# PSU_-_BUCK_LDO_CHARGER.net
KiCad netlist of a schematic drawn in Altium Designer
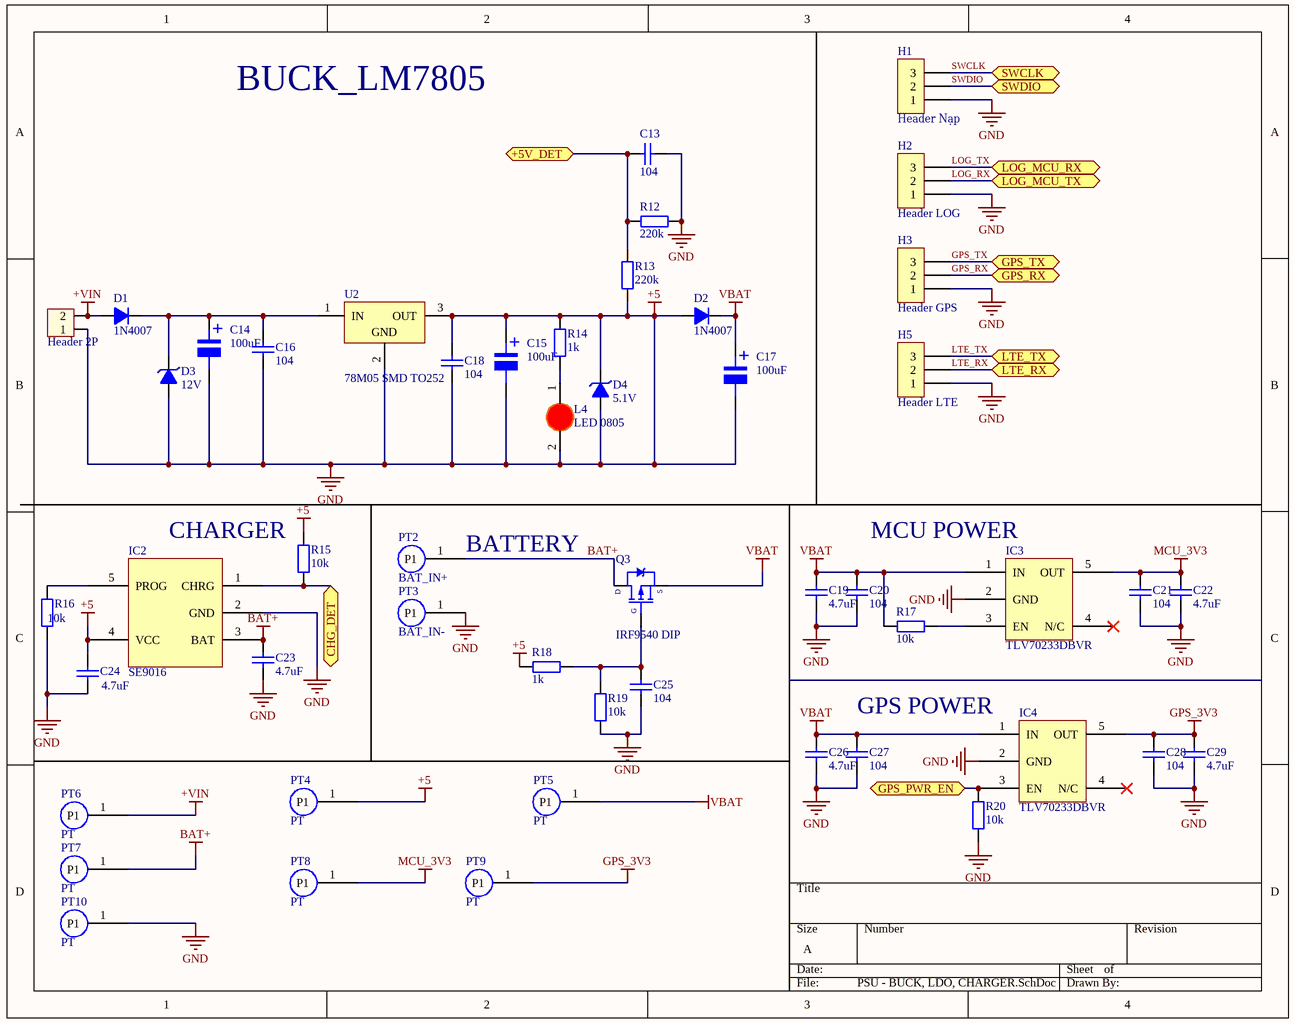
[diagram p0: PSU - BUCK, LDO, CHARGER.SchDoc]

(export (version "E")
  (design (tool "Eeschema 10.0.6"))
  (components
    (comp (ref "C13")
      (value "104")
      (footprint "tu 0805")
      (description "Dán")
      (libsource (lib "Altium_Lib_by_KhueNguyenCreator") (part "Tu 0805 104 50V 10%"))
    )
    (comp (ref "C14")
      (value "100uF")
      (footprint "tu nhom 6.3 (d)")
      (description "Dán")
      (libsource (lib "Altium_Lib_by_KhueNguyenCreator") (part "Tu Nhom 100uF 25V"))
    )
    (comp (ref "C15")
      (value "100uF")
      (footprint "tu nhom 6.3 (d)")
      (description "Dán")
      (libsource (lib "Altium_Lib_by_KhueNguyenCreator") (part "Tu Nhom 100uF 25V"))
    )
    (comp (ref "C16")
      (value "104")
      (footprint "tu 0805")
      (description "Dán")
      (libsource (lib "Altium_Lib_by_KhueNguyenCreator") (part "Tu 0805 104 50V 10%"))
    )
    (comp (ref "C17")
      (value "100uF")
      (footprint "tu nhom 6.3 (d)")
      (description "Dán")
      (libsource (lib "Altium_Lib_by_KhueNguyenCreator") (part "Tu Nhom 100uF 25V"))
    )
    (comp (ref "C18")
      (value "104")
      (footprint "tu 0805")
      (description "Dán")
      (libsource (lib "Altium_Lib_by_KhueNguyenCreator") (part "Tu 0805 104 50V 10%"))
    )
    (comp (ref "C19")
      (value "4.7uF")
      (footprint "tu 0805")
      (description "Dán")
      (libsource (lib "Altium_Lib_by_KhueNguyenCreator") (part "Tu 0805 475 25V 20%"))
    )
    (comp (ref "C20")
      (value "104")
      (footprint "tu 0805")
      (description "Dán")
      (libsource (lib "Altium_Lib_by_KhueNguyenCreator") (part "Tu 0805 104 50V 10%"))
    )
    (comp (ref "C21")
      (value "104")
      (footprint "tu 0805")
      (description "Dán")
      (libsource (lib "Altium_Lib_by_KhueNguyenCreator") (part "Tu 0805 104 50V 10%"))
    )
    (comp (ref "C22")
      (value "4.7uF")
      (footprint "tu 0805")
      (description "Dán")
      (libsource (lib "Altium_Lib_by_KhueNguyenCreator") (part "Tu 0805 475 25V 20%"))
    )
    (comp (ref "C23")
      (value "4.7uF")
      (footprint "tu 0805")
      (description "Dán")
      (libsource (lib "Altium_Lib_by_KhueNguyenCreator") (part "Tu 0805 475 25V 20%"))
    )
    (comp (ref "C24")
      (value "4.7uF")
      (footprint "tu 0805")
      (description "Dán")
      (libsource (lib "Altium_Lib_by_KhueNguyenCreator") (part "Tu 0805 475 25V 20%"))
    )
    (comp (ref "C25")
      (value "104")
      (footprint "tu 0805")
      (description "Dán")
      (libsource (lib "Altium_Lib_by_KhueNguyenCreator") (part "Tu 0805 104 50V 10%"))
    )
    (comp (ref "C26")
      (value "4.7uF")
      (footprint "tu 0805")
      (description "Dán")
      (libsource (lib "Altium_Lib_by_KhueNguyenCreator") (part "Tu 0805 475 25V 20%"))
    )
    (comp (ref "C27")
      (value "104")
      (footprint "tu 0805")
      (description "Dán")
      (libsource (lib "Altium_Lib_by_KhueNguyenCreator") (part "Tu 0805 104 50V 10%"))
    )
    (comp (ref "C28")
      (value "104")
      (footprint "tu 0805")
      (description "Dán")
      (libsource (lib "Altium_Lib_by_KhueNguyenCreator") (part "Tu 0805 104 50V 10%"))
    )
    (comp (ref "C29")
      (value "4.7uF")
      (footprint "tu 0805")
      (description "Dán")
      (libsource (lib "Altium_Lib_by_KhueNguyenCreator") (part "Tu 0805 475 25V 20%"))
    )
    (comp (ref "D1")
      (value "1N4007")
      (footprint "SODFL504X243-2N")
      (description "Cắm")
      (libsource (lib "Altium_Lib_by_KhueNguyenCreator") (part "Diode 1N4007"))
    )
    (comp (ref "D2")
      (value "1N4007")
      (footprint "SODFL504X243-2N")
      (description "Cắm")
      (libsource (lib "Altium_Lib_by_KhueNguyenCreator") (part "Diode 1N4007"))
    )
    (comp (ref "D3")
      (value "12V")
      (footprint "DIODE ZENNER SMD SOD80")
      (description "Dán")
      (libsource (lib "Altium_Lib_by_KhueNguyenCreator") (part "Diode Zener 12V"))
    )
    (comp (ref "D4")
      (value "5.1V")
      (footprint "DIODE ZENNER SMD SOD80")
      (description "Dán")
      (libsource (lib "Altium_Lib_by_KhueNguyenCreator") (part "Diode Zener 5.1V"))
    )
    (comp (ref "H1")
      (value "Header Nạp")
      (footprint "XH2.54M-3")
      (description "Cắm")
      (libsource (lib "Altium_Lib_by_KhueNguyenCreator") (part "Header 3P 2.54 Duc Thang"))
    )
    (comp (ref "H2")
      (value "Header LOG")
      (footprint "XH2.54M-3")
      (description "Cắm")
      (libsource (lib "Altium_Lib_by_KhueNguyenCreator") (part "Header 3P 2.54 Duc Thang"))
    )
    (comp (ref "H3")
      (value "Header GPS")
      (footprint "XH2.54M-3")
      (description "Cắm")
      (libsource (lib "Altium_Lib_by_KhueNguyenCreator") (part "Header 3P 2.54 Duc Thang"))
    )
    (comp (ref "H4")
      (value "Header 2P")
      (footprint "VH3.96M-2")
      (description "Cắm")
      (libsource (lib "Altium_Lib_by_KhueNguyenCreator") (part "Header 2P VH3.96 Duc Thang"))
    )
    (comp (ref "H5")
      (value "Header LTE")
      (footprint "XH2.54M-3")
      (description "Cắm")
      (libsource (lib "Altium_Lib_by_KhueNguyenCreator") (part "Header 3P 2.54 Duc Thang"))
    )
    (comp (ref "IC2")
      (value "SE9016")
      (footprint "SOT95P280X110-5N")
      (libsource (lib "Schlib2") (part "SE9016"))
    )
    (comp (ref "IC3")
      (value "TLV70233DBVR")
      (footprint "SOT95P280X145-5N")
      (libsource (lib "Schlib1") (part "TLV70233DBVR"))
    )
    (comp (ref "IC4")
      (value "TLV70233DBVR")
      (footprint "SOT95P280X145-5N")
      (libsource (lib "Schlib1") (part "TLV70233DBVR"))
    )
    (comp (ref "L4")
      (value "LED 0805")
      (footprint "LED-0805-Red")
      (description "Dán")
      (libsource (lib "Altium_Lib_by_KhueNguyenCreator") (part "LED 0805 Do"))
    )
    (comp (ref "PT2")
      (value "BAT_IN+")
      (footprint "Test pont")
      (libsource (lib "Test pont") (part "test pont"))
    )
    (comp (ref "PT3")
      (value "BAT_IN-")
      (footprint "Test pont")
      (libsource (lib "Test pont") (part "test pont"))
    )
    (comp (ref "PT4") (value "PT") (footprint "Test pont") (libsource (lib "Test pont") (part "test pont")))
    (comp (ref "PT5") (value "PT") (footprint "Test pont") (libsource (lib "Test pont") (part "test pont")))
    (comp (ref "PT6") (value "PT") (footprint "Test pont") (libsource (lib "Test pont") (part "test pont")))
    (comp (ref "PT7") (value "PT") (footprint "Test pont") (libsource (lib "Test pont") (part "test pont")))
    (comp (ref "PT8") (value "PT") (footprint "Test pont") (libsource (lib "Test pont") (part "test pont")))
    (comp (ref "PT9") (value "PT") (footprint "Test pont") (libsource (lib "Test pont") (part "test pont")))
    (comp (ref "PT10") (value "PT") (footprint "Test pont") (libsource (lib "Test pont") (part "test pont")))
    (comp (ref "Q3")
      (value "IRF9540 DIP")
      (footprint "DPAK254P1511X469-3N")
      (description "P-Channel Power MOSFET")
      (fields (field (name "PUBLISHER") "Altium Limited"))
      (libsource (lib "Altium_Lib_by_KhueNguyenCreator") (part "IRF9540 DIP"))
    )
    (comp (ref "R12")
      (value "220k")
      (footprint "tro smd 0805")
      (description "Dán")
      (libsource (lib "Altium_Lib_by_KhueNguyenCreator") (part "Tro 0805 5% 220k"))
    )
    (comp (ref "R13")
      (value "220k")
      (footprint "tro smd 0805")
      (description "Dán")
      (libsource (lib "Altium_Lib_by_KhueNguyenCreator") (part "Tro 0805 5% 220k"))
    )
    (comp (ref "R14")
      (value "1k")
      (footprint "tro smd 0805")
      (description "Dán")
      (libsource (lib "Altium_Lib_by_KhueNguyenCreator") (part "Tro 0805 1% 1k"))
    )
    (comp (ref "R15")
      (value "10k")
      (footprint "tro smd 0805")
      (description "Dán")
      (libsource (lib "Altium_Lib_by_KhueNguyenCreator") (part "Tro 0805 5% 10k"))
    )
    (comp (ref "R16")
      (value "10k")
      (footprint "tro smd 0805")
      (description "Dán")
      (libsource (lib "Altium_Lib_by_KhueNguyenCreator") (part "Tro 0805 5% 10k"))
    )
    (comp (ref "R17")
      (value "10k")
      (footprint "tro smd 0805")
      (description "Dán")
      (libsource (lib "Altium_Lib_by_KhueNguyenCreator") (part "Tro 0805 5% 10k"))
    )
    (comp (ref "R18")
      (value "1k")
      (footprint "tro smd 0805")
      (description "Dán")
      (libsource (lib "Altium_Lib_by_KhueNguyenCreator") (part "Tro 0805 1% 1k"))
    )
    (comp (ref "R19")
      (value "10k")
      (footprint "tro smd 0805")
      (description "Dán")
      (libsource (lib "Altium_Lib_by_KhueNguyenCreator") (part "Tro 0805 5% 10k"))
    )
    (comp (ref "R20")
      (value "10k")
      (footprint "tro smd 0805")
      (description "Dán")
      (libsource (lib "Altium_Lib_by_KhueNguyenCreator") (part "Tro 0805 5% 10k"))
    )
    (comp (ref "U2")
      (value "78M05 SMD TO252")
      (footprint "TO252")
      (description "Dán")
      (libsource (lib "Altium_Lib_by_KhueNguyenCreator") (part "78M05 SMD TO252"))
    )
  )
  (nets
    (net (code "1") (name "+5") (class "Default")
      (node (ref "C13") (pin "2") (pinfunction "2_2") (pintype "passive"))
      (node (ref "C14") (pin "2") (pinfunction "2_2") (pintype "passive"))
      (node (ref "C15") (pin "1") (pinfunction "1_1") (pintype "passive"))
      (node (ref "C15") (pin "2") (pinfunction "2_2") (pintype "passive"))
      (node (ref "C16") (pin "2") (pinfunction "2_2") (pintype "passive"))
      (node (ref "C17") (pin "2") (pinfunction "2_2") (pintype "passive"))
      (node (ref "C18") (pin "1") (pinfunction "1_1") (pintype "passive"))
      (node (ref "C18") (pin "2") (pinfunction "2_2") (pintype "passive"))
      (node (ref "C19") (pin "2") (pinfunction "2_2") (pintype "passive"))
      (node (ref "C20") (pin "2") (pinfunction "2_2") (pintype "passive"))
      (node (ref "C21") (pin "2") (pinfunction "2_2") (pintype "passive"))
      (node (ref "C22") (pin "2") (pinfunction "2_2") (pintype "passive"))
      (node (ref "C23") (pin "2") (pinfunction "2_2") (pintype "passive"))
      (node (ref "C24") (pin "1") (pinfunction "1_1") (pintype "passive"))
      (node (ref "C24") (pin "2") (pinfunction "2_2") (pintype "passive"))
      (node (ref "C25") (pin "2") (pinfunction "2_2") (pintype "passive"))
      (node (ref "C26") (pin "2") (pinfunction "2_2") (pintype "passive"))
      (node (ref "C27") (pin "2") (pinfunction "2_2") (pintype "passive"))
      (node (ref "C28") (pin "2") (pinfunction "2_2") (pintype "passive"))
      (node (ref "C29") (pin "2") (pinfunction "2_2") (pintype "passive"))
      (node (ref "D2") (pin "1") (pinfunction "A_1") (pintype "passive"))
      (node (ref "D3") (pin "1") (pinfunction "A_1") (pintype "passive"))
      (node (ref "D4") (pin "1") (pinfunction "A_1") (pintype "passive"))
      (node (ref "D4") (pin "2") (pinfunction "K_2") (pintype "passive"))
      (node (ref "H1") (pin "1") (pinfunction "1_1") (pintype "passive"))
      (node (ref "H2") (pin "1") (pinfunction "1_1") (pintype "passive"))
      (node (ref "H3") (pin "1") (pinfunction "1_1") (pintype "passive"))
      (node (ref "H4") (pin "1") (pinfunction "1_1") (pintype "passive"))
      (node (ref "H5") (pin "1") (pinfunction "1_1") (pintype "passive"))
      (node (ref "IC2") (pin "2") (pinfunction "GND_2") (pintype "passive"))
      (node (ref "IC2") (pin "4") (pinfunction "VCC_4") (pintype "passive"))
      (node (ref "IC3") (pin "2") (pinfunction "GND_2") (pintype "passive"))
      (node (ref "IC4") (pin "2") (pinfunction "GND_2") (pintype "passive"))
      (node (ref "L4") (pin "2") (pinfunction "K_2") (pintype "passive"))
      (node (ref "PT10") (pin "1") (pinfunction "P1_1") (pintype "passive"))
      (node (ref "PT3") (pin "1") (pinfunction "P1_1") (pintype "passive"))
      (node (ref "PT4") (pin "1") (pinfunction "P1_1") (pintype "passive"))
      (node (ref "R12") (pin "1") (pinfunction "1_1") (pintype "passive"))
      (node (ref "R13") (pin "1") (pinfunction "1_1") (pintype "passive"))
      (node (ref "R14") (pin "2") (pinfunction "2_2") (pintype "passive"))
      (node (ref "R15") (pin "2") (pinfunction "2_2") (pintype "passive"))
      (node (ref "R16") (pin "1") (pinfunction "1_1") (pintype "passive"))
      (node (ref "R18") (pin "1") (pinfunction "1_1") (pintype "passive"))
      (node (ref "R19") (pin "1") (pinfunction "1_1") (pintype "passive"))
      (node (ref "R20") (pin "1") (pinfunction "1_1") (pintype "passive"))
      (node (ref "U2") (pin "2") (pinfunction "GND_2") (pintype "power_in"))
      (node (ref "U2") (pin "3") (pinfunction "OUT_3") (pintype "power_in"))
    )
    (net (code "2") (name "+VIN") (class "Default")
      (node (ref "D1") (pin "1") (pinfunction "A_1") (pintype "passive"))
      (node (ref "H4") (pin "2") (pinfunction "2_2") (pintype "passive"))
      (node (ref "PT6") (pin "1") (pinfunction "P1_1") (pintype "passive"))
    )
    (net (code "3") (name "/+5V_DET") (class "Default")
      (node (ref "C13") (pin "1") (pinfunction "1_1") (pintype "passive"))
      (node (ref "R12") (pin "2") (pinfunction "2_2") (pintype "passive"))
      (node (ref "R13") (pin "2") (pinfunction "2_2") (pintype "passive"))
    )
    (net (code "4") (name "/CHG_DET") (class "Default")
      (node (ref "IC2") (pin "1") (pinfunction "CHRG_1") (pintype "passive"))
      (node (ref "R15") (pin "1") (pinfunction "1_1") (pintype "passive"))
    )
    (net (code "5") (name "/GPS_PWR_EN") (class "Default")
      (node (ref "IC4") (pin "3") (pinfunction "EN_3") (pintype "passive"))
      (node (ref "R20") (pin "2") (pinfunction "2_2") (pintype "passive"))
    )
    (net (code "6") (name "/GPS_RX") (class "Default")
      (node (ref "H3") (pin "2") (pinfunction "2_2") (pintype "passive"))
    )
    (net (code "7") (name "/GPS_TX") (class "Default")
      (node (ref "H3") (pin "3") (pinfunction "3_3") (pintype "passive"))
    )
    (net (code "8") (name "/LOG_RX") (class "Default")
      (node (ref "H2") (pin "2") (pinfunction "2_2") (pintype "passive"))
    )
    (net (code "9") (name "/LOG_TX") (class "Default")
      (node (ref "H2") (pin "3") (pinfunction "3_3") (pintype "passive"))
    )
    (net (code "10") (name "/LTE_RX") (class "Default")
      (node (ref "H5") (pin "2") (pinfunction "2_2") (pintype "passive"))
    )
    (net (code "11") (name "/LTE_TX") (class "Default")
      (node (ref "H5") (pin "3") (pinfunction "3_3") (pintype "passive"))
    )
    (net (code "12") (name "/SWCLK") (class "Default")
      (node (ref "H1") (pin "3") (pinfunction "3_3") (pintype "passive"))
    )
    (net (code "13") (name "/SWDIO") (class "Default")
      (node (ref "H1") (pin "2") (pinfunction "2_2") (pintype "passive"))
    )
    (net (code "14") (name "BAT+") (class "Default")
      (node (ref "C23") (pin "1") (pinfunction "1_1") (pintype "passive"))
      (node (ref "IC2") (pin "3") (pinfunction "BAT_3") (pintype "passive"))
      (node (ref "PT2") (pin "1") (pinfunction "P1_1") (pintype "passive"))
      (node (ref "PT7") (pin "1") (pinfunction "P1_1") (pintype "passive"))
      (node (ref "Q3") (pin "2") (pinfunction "D_2") (pintype "passive"))
    )
    (net (code "15") (name "GPS_3V3") (class "Default")
      (node (ref "C28") (pin "1") (pinfunction "1_1") (pintype "passive"))
      (node (ref "C29") (pin "1") (pinfunction "1_1") (pintype "passive"))
      (node (ref "IC4") (pin "5") (pinfunction "OUT_5") (pintype "passive"))
      (node (ref "PT9") (pin "1") (pinfunction "P1_1") (pintype "passive"))
    )
    (net (code "16") (name "MCU_3V3") (class "Default")
      (node (ref "C21") (pin "1") (pinfunction "1_1") (pintype "passive"))
      (node (ref "C22") (pin "1") (pinfunction "1_1") (pintype "passive"))
      (node (ref "IC3") (pin "5") (pinfunction "OUT_5") (pintype "passive"))
      (node (ref "PT8") (pin "1") (pinfunction "P1_1") (pintype "passive"))
    )
    (net (code "17") (name "Net-(D1-K)") (class "Default")
      (node (ref "C14") (pin "1") (pinfunction "1_1") (pintype "passive"))
      (node (ref "C16") (pin "1") (pinfunction "1_1") (pintype "passive"))
      (node (ref "D1") (pin "2") (pinfunction "K_2") (pintype "passive"))
      (node (ref "D3") (pin "2") (pinfunction "K_2") (pintype "passive"))
      (node (ref "U2") (pin "1") (pinfunction "IN_1") (pintype "power_in"))
    )
    (net (code "18") (name "Net-(IC2-PROG)") (class "Default")
      (node (ref "IC2") (pin "5") (pinfunction "PROG_5") (pintype "passive"))
      (node (ref "R16") (pin "2") (pinfunction "2_2") (pintype "passive"))
    )
    (net (code "19") (name "Net-(IC3-EN)") (class "Default")
      (node (ref "IC3") (pin "3") (pinfunction "EN_3") (pintype "passive"))
      (node (ref "R17") (pin "2") (pinfunction "2_2") (pintype "passive"))
    )
    (net (code "20") (name "Net-(L4-A)") (class "Default")
      (node (ref "L4") (pin "1") (pinfunction "A_1") (pintype "passive"))
      (node (ref "R14") (pin "1") (pinfunction "1_1") (pintype "passive"))
    )
    (net (code "21") (name "Net-(Q3-G)") (class "Default")
      (node (ref "C25") (pin "1") (pinfunction "1_1") (pintype "passive"))
      (node (ref "Q3") (pin "1") (pinfunction "G_1") (pintype "passive"))
      (node (ref "R18") (pin "2") (pinfunction "2_2") (pintype "passive"))
      (node (ref "R19") (pin "2") (pinfunction "2_2") (pintype "passive"))
    )
    (net (code "22") (name "VBAT") (class "Default")
      (node (ref "C17") (pin "1") (pinfunction "1_1") (pintype "passive"))
      (node (ref "C19") (pin "1") (pinfunction "1_1") (pintype "passive"))
      (node (ref "C20") (pin "1") (pinfunction "1_1") (pintype "passive"))
      (node (ref "C26") (pin "1") (pinfunction "1_1") (pintype "passive"))
      (node (ref "C27") (pin "1") (pinfunction "1_1") (pintype "passive"))
      (node (ref "D2") (pin "2") (pinfunction "K_2") (pintype "passive"))
      (node (ref "IC3") (pin "1") (pinfunction "IN_1") (pintype "passive"))
      (node (ref "IC4") (pin "1") (pinfunction "IN_1") (pintype "passive"))
      (node (ref "PT5") (pin "1") (pinfunction "P1_1") (pintype "passive"))
      (node (ref "Q3") (pin "3") (pinfunction "S_3") (pintype "passive"))
      (node (ref "R17") (pin "1") (pinfunction "1_1") (pintype "passive"))
    )
    (net (code "23") (name "unconnected-(IC3-N{slash}C-Pad4)") (class "Default")
      (node (ref "IC3") (pin "4") (pinfunction "N/C_4") (pintype "passive+no_connect"))
    )
    (net (code "24") (name "unconnected-(IC4-N{slash}C-Pad4)") (class "Default")
      (node (ref "IC4") (pin "4") (pinfunction "N/C_4") (pintype "passive+no_connect"))
    )
  )
)
